# PCB_Design.net
KiCad netlist of a schematic drawn in EAGLE
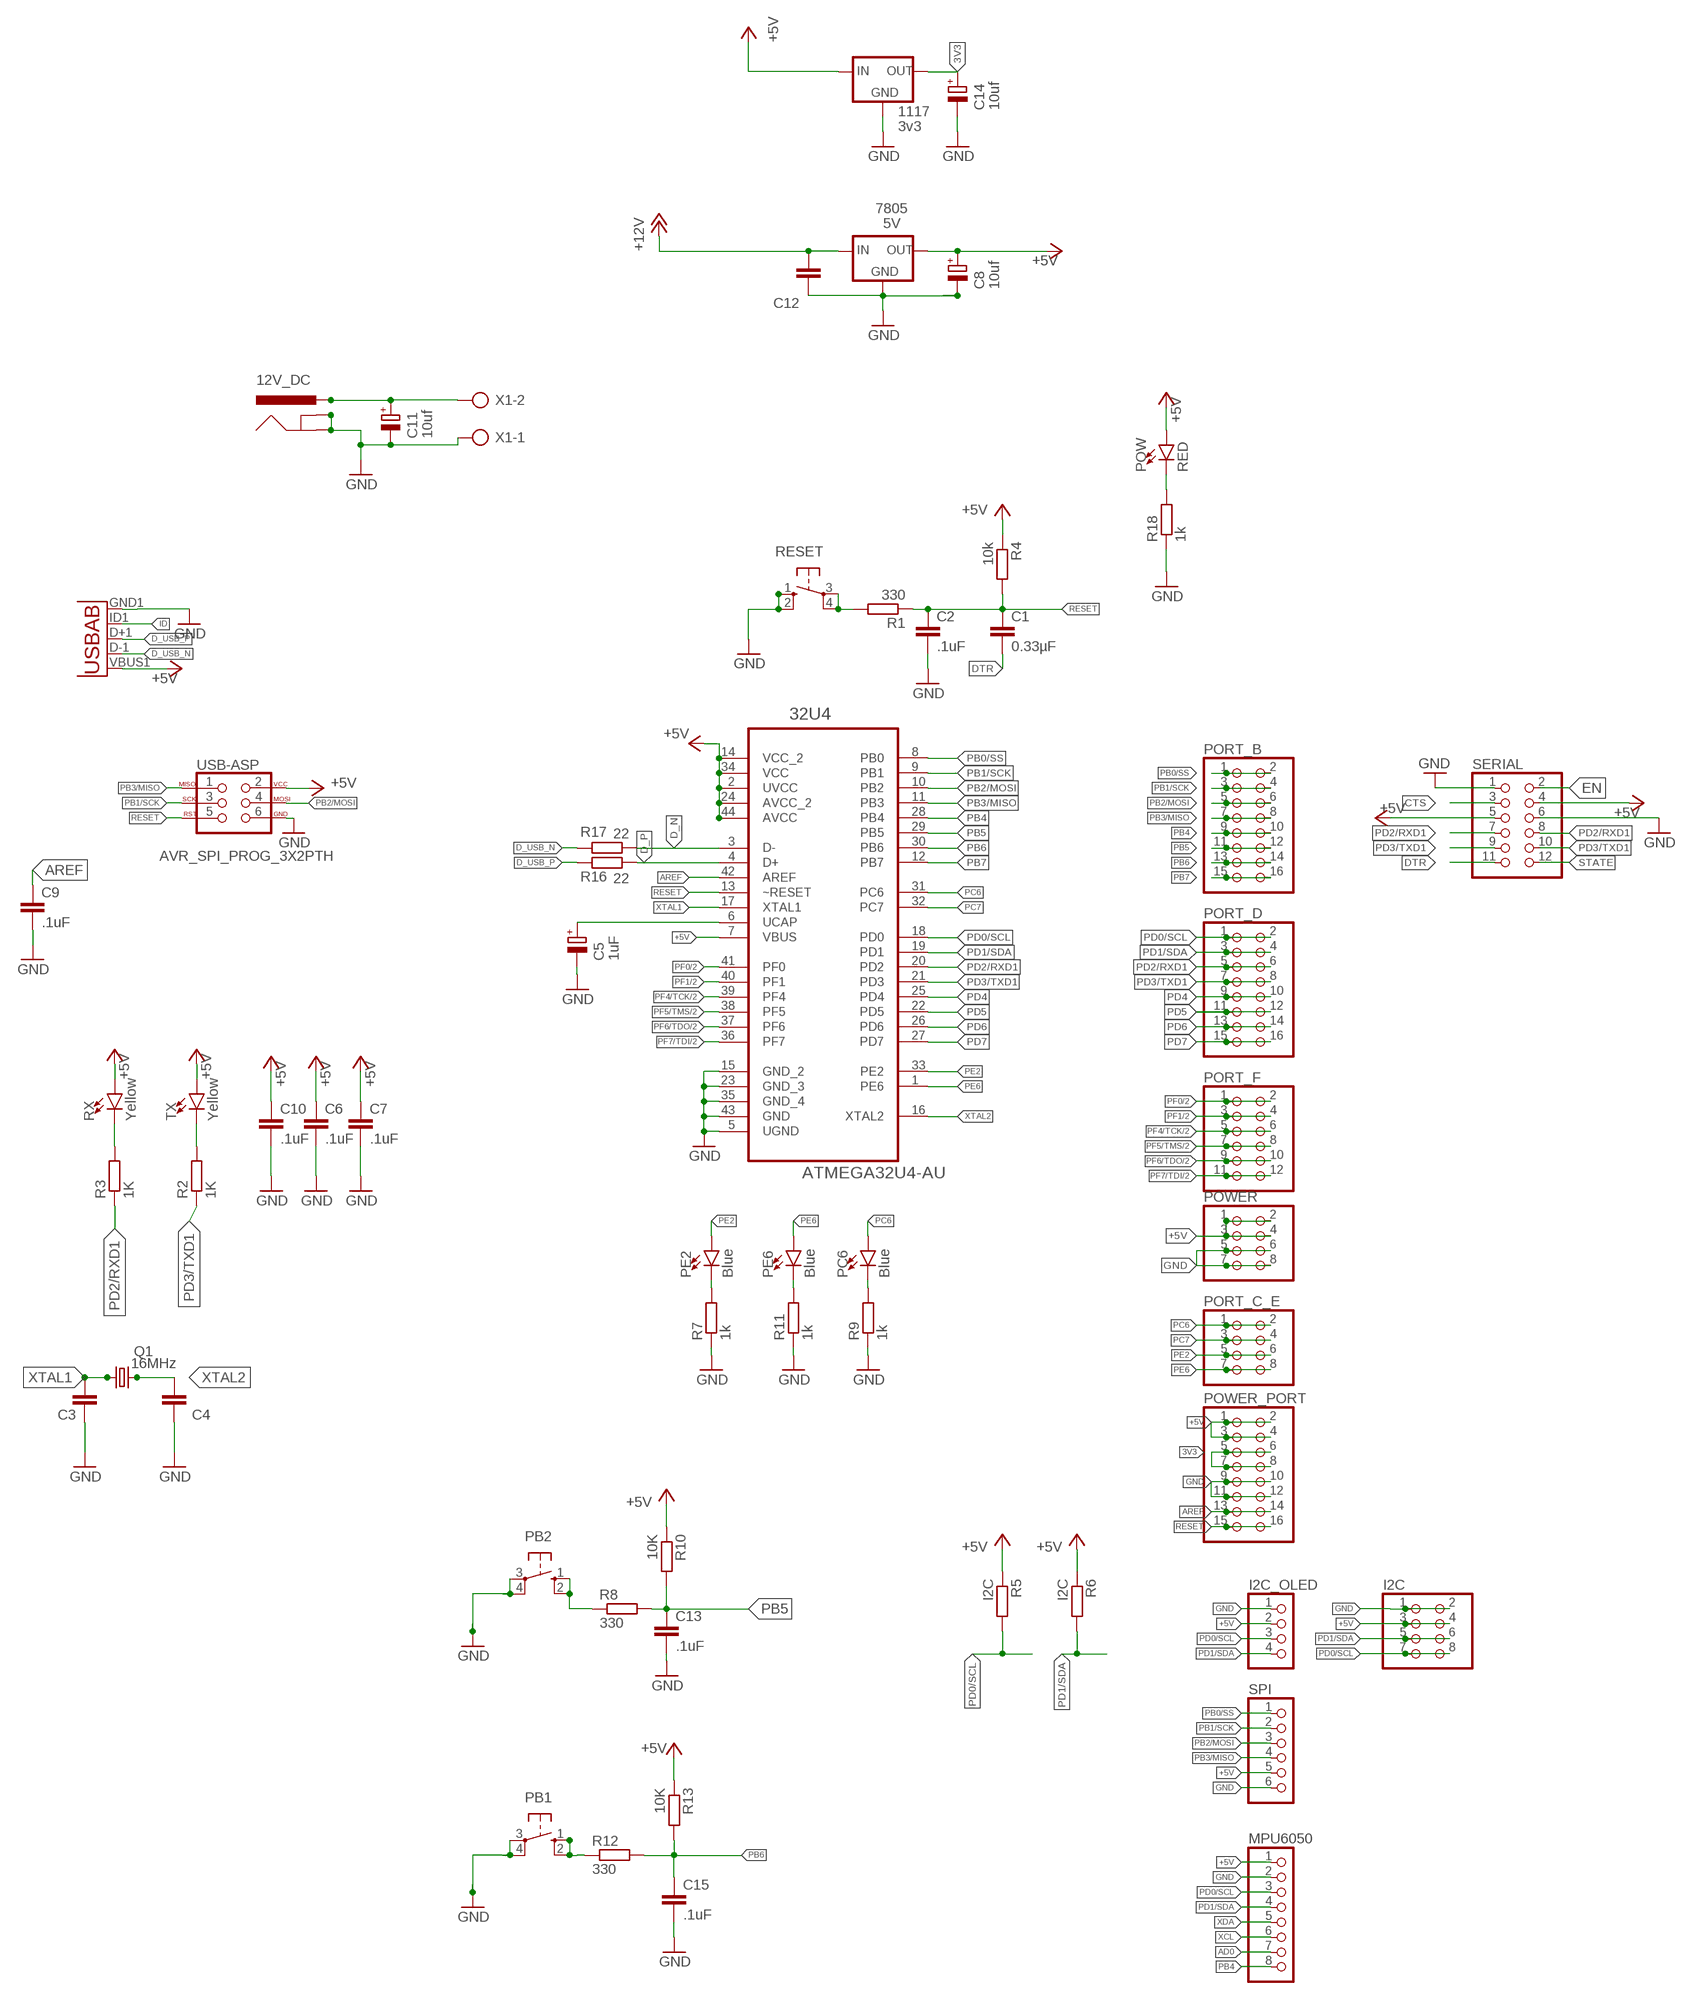
[diagram p0: schematic, sheet 1]
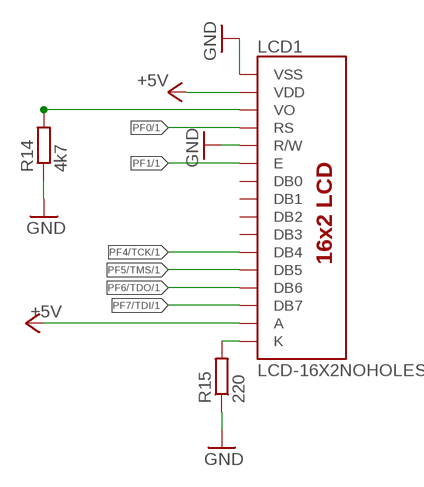
[diagram p1: schematic, sheet 2]

(export (version "E")
  (design (tool "Eeschema 10.0.6"))
  (components
    (comp (ref "LCD1")
      (value "LCD-16X2NOHOLES")
      (footprint "eagle-import:LCD-16X2_NOHOLESNOSILK")
      (libsource (lib "eagle-import") (part "LCD-16X2NOHOLES"))
    )
    (comp (ref "R14")
      (value "4k7")
      (footprint "eagle-import:M0805")
      (libsource (lib "eagle-import") (part "R-EU_M0805"))
    )
    (comp (ref "R15")
      (value "220")
      (footprint "eagle-import:M0805")
      (libsource (lib "eagle-import") (part "R-EU_M0805"))
    )
    (comp (ref "12V_DC")
      (value "POWER_JACK")
      (footprint "eagle-import:POWER_JACK_PTH")
      (fields (field (name "MF") "MULTICOMP") (field (name "MPN") "SPC21365"))
      (libsource (lib "eagle-import") (part "POWER_JACK"))
    )
    (comp (ref "32U4")
      (value "ATMEGA32U4-AU")
      (footprint "eagle-import:QFP80P1200X1200X120-44N")
      (fields (field (name "MF") "Microchip"))
      (libsource (lib "eagle-import") (part "ATMEGA32U4-AU"))
    )
    (comp (ref "1117")
      (value "3v3")
      (footprint "eagle-import:SOT223")
      (libsource (lib "eagle-import") (part "V_REG_LD1117VXXLD1117-SMD"))
    )
    (comp (ref "7805")
      (value "5V")
      (footprint "eagle-import:TO-252")
      (libsource (lib "eagle-import") (part "V_REG_78XX7812"))
    )
    (comp (ref "C1")
      (value "0.33µF")
      (footprint "eagle-import:C0805K")
      (libsource (lib "eagle-import") (part "C-EUC0805K"))
    )
    (comp (ref "C2")
      (value ".1uF")
      (footprint "eagle-import:C0805K")
      (libsource (lib "eagle-import") (part "C-EUC0805K"))
    )
    (comp (ref "C3")
      (value "22pF")
      (footprint "eagle-import:C0805K")
      (libsource (lib "eagle-import") (part "C-EUC0805K"))
    )
    (comp (ref "C4")
      (value "22pF")
      (footprint "eagle-import:C0805K")
      (libsource (lib "eagle-import") (part "C-EUC0805K"))
    )
    (comp (ref "C5")
      (value "1uF")
      (footprint "eagle-import:E2,5-6")
      (libsource (lib "eagle-import") (part "CPOL-EUE2.5-6"))
    )
    (comp (ref "C6")
      (value ".1uF")
      (footprint "eagle-import:C0805K")
      (libsource (lib "eagle-import") (part "C-EUC0805K"))
    )
    (comp (ref "C7")
      (value ".1uF")
      (footprint "eagle-import:C0805K")
      (libsource (lib "eagle-import") (part "C-EUC0805K"))
    )
    (comp (ref "C8")
      (value "10uf")
      (footprint "eagle-import:E2,5-6")
      (libsource (lib "eagle-import") (part "CPOL-EUE2.5-6"))
    )
    (comp (ref "C9")
      (value ".1uF")
      (footprint "eagle-import:C0805K")
      (libsource (lib "eagle-import") (part "C-EUC0805K"))
    )
    (comp (ref "C10")
      (value ".1uF")
      (footprint "eagle-import:C0805K")
      (libsource (lib "eagle-import") (part "C-EUC0805K"))
    )
    (comp (ref "C11")
      (value "10uf")
      (footprint "eagle-import:E2,5-6")
      (libsource (lib "eagle-import") (part "CPOL-EUE2.5-6"))
    )
    (comp (ref "C12")
      (value ".1uf")
      (footprint "eagle-import:C0805K")
      (libsource (lib "eagle-import") (part "C-EUC0805K"))
    )
    (comp (ref "C13")
      (value ".1uF")
      (footprint "eagle-import:C0805K")
      (libsource (lib "eagle-import") (part "C-EUC0805K"))
    )
    (comp (ref "C14")
      (value "10uf")
      (footprint "eagle-import:E2,5-6")
      (libsource (lib "eagle-import") (part "CPOL-EUE2.5-6"))
    )
    (comp (ref "C15")
      (value ".1uF")
      (footprint "eagle-import:C0805K")
      (libsource (lib "eagle-import") (part "C-EUC0805K"))
    )
    (comp (ref "I2C")
      (value "PINHD-2X4")
      (footprint "eagle-import:2X04")
      (libsource (lib "eagle-import") (part "PINHD-2X4"))
    )
    (comp (ref "I2C_OLED")
      (value "PINHD-1X4")
      (footprint "eagle-import:1X04")
      (libsource (lib "eagle-import") (part "PINHD-1X4"))
    )
    (comp (ref "MPU6050")
      (value "PINHD-1X8")
      (footprint "eagle-import:1X08")
      (libsource (lib "eagle-import") (part "PINHD-1X8"))
    )
    (comp (ref "PB1")
      (value "10-XX")
      (footprint "eagle-import:B3F-10XX")
      (fields (field (name "MPN") "B3F-1000") (field (name "MF") "OMRON"))
      (libsource (lib "eagle-import") (part "10-XX"))
    )
    (comp (ref "PB2")
      (value "10-XX")
      (footprint "eagle-import:B3F-10XX")
      (fields (field (name "MPN") "B3F-1000") (field (name "MF") "OMRON"))
      (libsource (lib "eagle-import") (part "10-XX"))
    )
    (comp (ref "PC6")
      (value "Blue")
      (footprint "eagle-import:LED-0603")
      (libsource (lib "eagle-import") (part "LED-BLUE0603"))
    )
    (comp (ref "PE2")
      (value "Blue")
      (footprint "eagle-import:LED-0603")
      (libsource (lib "eagle-import") (part "LED-BLUE0603"))
    )
    (comp (ref "PE6")
      (value "Blue")
      (footprint "eagle-import:LED-0603")
      (libsource (lib "eagle-import") (part "LED-BLUE0603"))
    )
    (comp (ref "PORT_B")
      (value "PINHD-2X8")
      (footprint "eagle-import:2X08")
      (libsource (lib "eagle-import") (part "PINHD-2X8"))
    )
    (comp (ref "PORT_C_E")
      (value "PINHD-2X4")
      (footprint "eagle-import:2X04")
      (libsource (lib "eagle-import") (part "PINHD-2X4"))
    )
    (comp (ref "PORT_D")
      (value "PINHD-2X8")
      (footprint "eagle-import:2X08")
      (libsource (lib "eagle-import") (part "PINHD-2X8"))
    )
    (comp (ref "PORT_F")
      (value "PINHD-2X6")
      (footprint "eagle-import:2X06")
      (libsource (lib "eagle-import") (part "PINHD-2X6"))
    )
    (comp (ref "POW")
      (value "RED")
      (footprint "eagle-import:LED-0603")
      (libsource (lib "eagle-import") (part "LED-BLUE0603"))
    )
    (comp (ref "POWER")
      (value "PINHD-2X4")
      (footprint "eagle-import:2X04")
      (libsource (lib "eagle-import") (part "PINHD-2X4"))
    )
    (comp (ref "POWER_PORT")
      (value "PINHD-2X8")
      (footprint "eagle-import:2X08")
      (libsource (lib "eagle-import") (part "PINHD-2X8"))
    )
    (comp (ref "Q1")
      (value "16MHz")
      (footprint "eagle-import:HC49U70")
      (libsource (lib "eagle-import") (part "CRYSTALHC49U70"))
    )
    (comp (ref "R1")
      (value "330")
      (footprint "eagle-import:M0805")
      (libsource (lib "eagle-import") (part "R-EU_M0805"))
    )
    (comp (ref "R2")
      (value "1K")
      (footprint "eagle-import:M0805")
      (libsource (lib "eagle-import") (part "R-EU_M0805"))
    )
    (comp (ref "R3")
      (value "1K")
      (footprint "eagle-import:M0805")
      (libsource (lib "eagle-import") (part "R-EU_M0805"))
    )
    (comp (ref "R4")
      (value "10k")
      (footprint "eagle-import:M0805")
      (libsource (lib "eagle-import") (part "R-EU_M0805"))
    )
    (comp (ref "R5")
      (value "I2C")
      (footprint "eagle-import:M0805")
      (libsource (lib "eagle-import") (part "R-EU_M0805"))
    )
    (comp (ref "R6")
      (value "I2C")
      (footprint "eagle-import:M0805")
      (libsource (lib "eagle-import") (part "R-EU_M0805"))
    )
    (comp (ref "R7")
      (value "1k")
      (footprint "eagle-import:M0805")
      (libsource (lib "eagle-import") (part "R-EU_M0805"))
    )
    (comp (ref "R8")
      (value "330")
      (footprint "eagle-import:M0805")
      (libsource (lib "eagle-import") (part "R-EU_M0805"))
    )
    (comp (ref "R9")
      (value "1k")
      (footprint "eagle-import:M0805")
      (libsource (lib "eagle-import") (part "R-EU_M0805"))
    )
    (comp (ref "R10")
      (value "10K")
      (footprint "eagle-import:M0805")
      (libsource (lib "eagle-import") (part "R-EU_M0805"))
    )
    (comp (ref "R11")
      (value "1k")
      (footprint "eagle-import:M0805")
      (libsource (lib "eagle-import") (part "R-EU_M0805"))
    )
    (comp (ref "R12")
      (value "330")
      (footprint "eagle-import:M0805")
      (libsource (lib "eagle-import") (part "R-EU_M0805"))
    )
    (comp (ref "R13")
      (value "10K")
      (footprint "eagle-import:M0805")
      (libsource (lib "eagle-import") (part "R-EU_M0805"))
    )
    (comp (ref "R16")
      (value "22")
      (footprint "eagle-import:M0805")
      (libsource (lib "eagle-import") (part "R-EU_M0805"))
    )
    (comp (ref "R17")
      (value "22")
      (footprint "eagle-import:M0805")
      (libsource (lib "eagle-import") (part "R-EU_M0805"))
    )
    (comp (ref "R18")
      (value "1k")
      (footprint "eagle-import:M0805")
      (libsource (lib "eagle-import") (part "R-EU_M0805"))
    )
    (comp (ref "RESET")
      (value "10-XX")
      (footprint "eagle-import:B3F-10XX")
      (fields (field (name "MPN") "B3F-1000") (field (name "MF") "OMRON"))
      (libsource (lib "eagle-import") (part "10-XX"))
    )
    (comp (ref "RX")
      (value "Yellow")
      (footprint "eagle-import:LED-0603")
      (libsource (lib "eagle-import") (part "LED-BLUE0603"))
    )
    (comp (ref "SERIAL")
      (value "PINHD-2X6")
      (footprint "eagle-import:2X06")
      (libsource (lib "eagle-import") (part "PINHD-2X6"))
    )
    (comp (ref "SPI")
      (value "PINHD-1X6")
      (footprint "eagle-import:1X06")
      (libsource (lib "eagle-import") (part "PINHD-1X6"))
    )
    (comp (ref "TX")
      (value "Yellow")
      (footprint "eagle-import:LED-0603")
      (libsource (lib "eagle-import") (part "LED-BLUE0603"))
    )
    (comp (ref "U1")
      (value "USB\"\"")
      (footprint "eagle-import:USB-MICRO-SMD")
      (libsource (lib "eagle-import") (part "USB{dblquote}{dblquote}"))
    )
    (comp (ref "USB-ASP")
      (value "AVR_SPI_PROG_3X2PTH")
      (footprint "eagle-import:2X3")
      (libsource (lib "eagle-import") (part "AVR_SPI_PROG_3X2PTH"))
    )
    (comp (ref "X1")
      (value "AK500/2-H")
      (footprint "eagle-import:AK500_2-H")
      (libsource (lib "eagle-import") (part "AK500/2-H"))
    )
  )
  (nets
    (net (code "1") (name "+5V") (class "Default")
      (node (ref "1117") (pin "3") (pinfunction "IN_3") (pintype "input"))
      (node (ref "32U4") (pin "14") (pinfunction "VCC_2_14") (pintype "power_in"))
      (node (ref "32U4") (pin "2") (pinfunction "UVCC_2") (pintype "power_in"))
      (node (ref "32U4") (pin "24") (pinfunction "AVCC_2_24") (pintype "power_in"))
      (node (ref "32U4") (pin "34") (pinfunction "VCC_34") (pintype "power_in"))
      (node (ref "32U4") (pin "44") (pinfunction "AVCC_44") (pintype "power_in"))
      (node (ref "32U4") (pin "7") (pinfunction "VBUS_7") (pintype "input"))
      (node (ref "7805") (pin "2") (pinfunction "OUT_2") (pintype "passive"))
      (node (ref "C10") (pin "1") (pinfunction "1_1") (pintype "passive"))
      (node (ref "C6") (pin "1") (pinfunction "1_1") (pintype "passive"))
      (node (ref "C7") (pin "1") (pinfunction "1_1") (pintype "passive"))
      (node (ref "C8") (pin "+") (pinfunction "+_+") (pintype "passive"))
      (node (ref "I2C") (pin "3") (pinfunction "3_3") (pintype "passive"))
      (node (ref "I2C") (pin "4") (pinfunction "4_4") (pintype "passive"))
      (node (ref "I2C_OLED") (pin "2") (pinfunction "2_2") (pintype "passive"))
      (node (ref "LCD1") (pin "15") (pinfunction "A_15") (pintype "power_in"))
      (node (ref "LCD1") (pin "2") (pinfunction "VDD_2") (pintype "power_in"))
      (node (ref "MPU6050") (pin "1") (pinfunction "1_1") (pintype "passive"))
      (node (ref "POW") (pin "A") (pinfunction "A_A") (pintype "passive"))
      (node (ref "POWER") (pin "1") (pinfunction "1_1") (pintype "passive"))
      (node (ref "POWER") (pin "2") (pinfunction "2_2") (pintype "passive"))
      (node (ref "POWER") (pin "3") (pinfunction "3_3") (pintype "passive"))
      (node (ref "POWER") (pin "4") (pinfunction "4_4") (pintype "passive"))
      (node (ref "POWER_PORT") (pin "1") (pinfunction "1_1") (pintype "passive"))
      (node (ref "POWER_PORT") (pin "2") (pinfunction "2_2") (pintype "passive"))
      (node (ref "POWER_PORT") (pin "3") (pinfunction "3_3") (pintype "passive"))
      (node (ref "POWER_PORT") (pin "4") (pinfunction "4_4") (pintype "passive"))
      (node (ref "R10") (pin "1") (pinfunction "1_1") (pintype "passive"))
      (node (ref "R13") (pin "1") (pinfunction "1_1") (pintype "passive"))
      (node (ref "R4") (pin "1") (pinfunction "1_1") (pintype "passive"))
      (node (ref "R5") (pin "1") (pinfunction "1_1") (pintype "passive"))
      (node (ref "R6") (pin "1") (pinfunction "1_1") (pintype "passive"))
      (node (ref "RX") (pin "A") (pinfunction "A_A") (pintype "passive"))
      (node (ref "SERIAL") (pin "4") (pinfunction "4_4") (pintype "passive"))
      (node (ref "SERIAL") (pin "5") (pinfunction "5_5") (pintype "passive"))
      (node (ref "SPI") (pin "5") (pinfunction "5_5") (pintype "passive"))
      (node (ref "TX") (pin "A") (pinfunction "A_A") (pintype "passive"))
      (node (ref "U1") (pin "VBUS1") (pinfunction "VBUS_VBUS1") (pintype "bidirectional"))
      (node (ref "USB-ASP") (pin "2") (pinfunction "2_2") (pintype "passive"))
    )
    (net (code "2") (name "+12V") (class "Default")
      (node (ref "12V_DC") (pin "PWR") (pinfunction "PWR_PWR") (pintype "bidirectional"))
      (node (ref "7805") (pin "1") (pinfunction "IN_1") (pintype "input"))
      (node (ref "C11") (pin "+") (pinfunction "+_+") (pintype "passive"))
      (node (ref "C12") (pin "1") (pinfunction "1_1") (pintype "passive"))
      (node (ref "X1") (pin "2") (pinfunction "KL_2") (pintype "passive"))
    )
    (net (code "3") (name "3V3") (class "Default")
      (node (ref "1117") (pin "2") (pinfunction "OUT_2") (pintype "passive"))
      (node (ref "C14") (pin "+") (pinfunction "+_+") (pintype "passive"))
      (node (ref "POWER_PORT") (pin "5") (pinfunction "5_5") (pintype "passive"))
      (node (ref "POWER_PORT") (pin "6") (pinfunction "6_6") (pintype "passive"))
      (node (ref "POWER_PORT") (pin "7") (pinfunction "7_7") (pintype "passive"))
      (node (ref "POWER_PORT") (pin "8") (pinfunction "8_8") (pintype "passive"))
    )
    (net (code "4") (name "AD0") (class "Default")
      (node (ref "MPU6050") (pin "7") (pinfunction "7_7") (pintype "passive"))
    )
    (net (code "5") (name "AREF") (class "Default")
      (node (ref "32U4") (pin "42") (pinfunction "AREF_42") (pintype "input"))
      (node (ref "C9") (pin "1") (pinfunction "1_1") (pintype "passive"))
      (node (ref "POWER_PORT") (pin "13") (pinfunction "13_13") (pintype "passive"))
      (node (ref "POWER_PORT") (pin "14") (pinfunction "14_14") (pintype "passive"))
    )
    (net (code "6") (name "CTS") (class "Default")
      (node (ref "SERIAL") (pin "3") (pinfunction "3_3") (pintype "passive"))
    )
    (net (code "7") (name "DTR") (class "Default")
      (node (ref "C1") (pin "2") (pinfunction "2_2") (pintype "passive"))
      (node (ref "SERIAL") (pin "11") (pinfunction "11_11") (pintype "passive"))
    )
    (net (code "8") (name "D_N") (class "Default")
      (node (ref "32U4") (pin "3") (pinfunction "D-_3") (pintype "passive"))
      (node (ref "R17") (pin "1") (pinfunction "1_1") (pintype "passive"))
    )
    (net (code "9") (name "D_P") (class "Default")
      (node (ref "32U4") (pin "4") (pinfunction "D+_4") (pintype "passive"))
      (node (ref "R16") (pin "1") (pinfunction "1_1") (pintype "passive"))
    )
    (net (code "10") (name "D_USB_N") (class "Default")
      (node (ref "R17") (pin "2") (pinfunction "2_2") (pintype "passive"))
      (node (ref "U1") (pin "D-1") (pinfunction "D-_D-1") (pintype "bidirectional"))
    )
    (net (code "11") (name "D_USB_P") (class "Default")
      (node (ref "R16") (pin "2") (pinfunction "2_2") (pintype "passive"))
      (node (ref "U1") (pin "D+1") (pinfunction "D+_D+1") (pintype "bidirectional"))
    )
    (net (code "12") (name "EN") (class "Default")
      (node (ref "SERIAL") (pin "2") (pinfunction "2_2") (pintype "passive"))
    )
    (net (code "13") (name "GND") (class "Default")
      (node (ref "1117") (pin "1") (pinfunction "GND_1") (pintype "input"))
      (node (ref "12V_DC") (pin "GND") (pinfunction "GND_GND") (pintype "bidirectional"))
      (node (ref "12V_DC") (pin "GNDBREAK") (pinfunction "GNDBREAK_GNDBREAK") (pintype "bidirectional"))
      (node (ref "32U4") (pin "15") (pinfunction "GND_2_15") (pintype "passive"))
      (node (ref "32U4") (pin "23") (pinfunction "GND_3_23") (pintype "passive"))
      (node (ref "32U4") (pin "35") (pinfunction "GND_4_35") (pintype "passive"))
      (node (ref "32U4") (pin "43") (pinfunction "GND_43") (pintype "passive"))
      (node (ref "32U4") (pin "5") (pinfunction "UGND_5") (pintype "passive"))
      (node (ref "7805") (pin "3") (pinfunction "GND_3") (pintype "input"))
      (node (ref "C10") (pin "2") (pinfunction "2_2") (pintype "passive"))
      (node (ref "C11") (pin "-") (pinfunction "-_-") (pintype "passive"))
      (node (ref "C12") (pin "2") (pinfunction "2_2") (pintype "passive"))
      (node (ref "C13") (pin "2") (pinfunction "2_2") (pintype "passive"))
      (node (ref "C14") (pin "-") (pinfunction "-_-") (pintype "passive"))
      (node (ref "C15") (pin "2") (pinfunction "2_2") (pintype "passive"))
      (node (ref "C2") (pin "2") (pinfunction "2_2") (pintype "passive"))
      (node (ref "C3") (pin "1") (pinfunction "1_1") (pintype "passive"))
      (node (ref "C4") (pin "1") (pinfunction "1_1") (pintype "passive"))
      (node (ref "C5") (pin "-") (pinfunction "-_-") (pintype "passive"))
      (node (ref "C6") (pin "2") (pinfunction "2_2") (pintype "passive"))
      (node (ref "C7") (pin "2") (pinfunction "2_2") (pintype "passive"))
      (node (ref "C8") (pin "-") (pinfunction "-_-") (pintype "passive"))
      (node (ref "C9") (pin "2") (pinfunction "2_2") (pintype "passive"))
      (node (ref "I2C") (pin "1") (pinfunction "1_1") (pintype "passive"))
      (node (ref "I2C") (pin "2") (pinfunction "2_2") (pintype "passive"))
      (node (ref "I2C_OLED") (pin "1") (pinfunction "1_1") (pintype "passive"))
      (node (ref "LCD1") (pin "1") (pinfunction "VSS_1") (pintype "power_in"))
      (node (ref "LCD1") (pin "5") (pinfunction "R/W_5") (pintype "input"))
      (node (ref "MPU6050") (pin "2") (pinfunction "2_2") (pintype "passive"))
      (node (ref "PB1") (pin "3") (pinfunction "P_3") (pintype "passive"))
      (node (ref "PB1") (pin "4") (pinfunction "P1_4") (pintype "passive"))
      (node (ref "PB2") (pin "3") (pinfunction "P_3") (pintype "passive"))
      (node (ref "PB2") (pin "4") (pinfunction "P1_4") (pintype "passive"))
      (node (ref "POWER") (pin "5") (pinfunction "5_5") (pintype "passive"))
      (node (ref "POWER") (pin "6") (pinfunction "6_6") (pintype "passive"))
      (node (ref "POWER") (pin "7") (pinfunction "7_7") (pintype "passive"))
      (node (ref "POWER") (pin "8") (pinfunction "8_8") (pintype "passive"))
      (node (ref "POWER_PORT") (pin "10") (pinfunction "10_10") (pintype "passive"))
      (node (ref "POWER_PORT") (pin "11") (pinfunction "11_11") (pintype "passive"))
      (node (ref "POWER_PORT") (pin "12") (pinfunction "12_12") (pintype "passive"))
      (node (ref "POWER_PORT") (pin "9") (pinfunction "9_9") (pintype "passive"))
      (node (ref "R11") (pin "1") (pinfunction "1_1") (pintype "passive"))
      (node (ref "R14") (pin "1") (pinfunction "1_1") (pintype "passive"))
      (node (ref "R15") (pin "1") (pinfunction "1_1") (pintype "passive"))
      (node (ref "R18") (pin "1") (pinfunction "1_1") (pintype "passive"))
      (node (ref "R7") (pin "1") (pinfunction "1_1") (pintype "passive"))
      (node (ref "R9") (pin "1") (pinfunction "1_1") (pintype "passive"))
      (node (ref "RESET") (pin "1") (pinfunction "S_1") (pintype "passive"))
      (node (ref "RESET") (pin "2") (pinfunction "S1_2") (pintype "passive"))
      (node (ref "SERIAL") (pin "1") (pinfunction "1_1") (pintype "passive"))
      (node (ref "SERIAL") (pin "6") (pinfunction "6_6") (pintype "passive"))
      (node (ref "SPI") (pin "6") (pinfunction "6_6") (pintype "passive"))
      (node (ref "U1") (pin "GND1") (pinfunction "GND_GND1") (pintype "bidirectional"))
      (node (ref "USB-ASP") (pin "6") (pinfunction "6_6") (pintype "passive"))
      (node (ref "X1") (pin "1") (pinfunction "KL_1") (pintype "passive"))
    )
    (net (code "14") (name "ID") (class "Default")
      (node (ref "U1") (pin "ID1") (pinfunction "USBID_ID1") (pintype "bidirectional"))
    )
    (net (code "15") (name "Net-(32U4-UCAP)") (class "Default")
      (node (ref "32U4") (pin "6") (pinfunction "UCAP_6") (pintype "power_in"))
      (node (ref "C5") (pin "+") (pinfunction "+_+") (pintype "passive"))
    )
    (net (code "16") (name "Net-(LCD1-K)") (class "Default")
      (node (ref "LCD1") (pin "16") (pinfunction "K_16") (pintype "power_in"))
      (node (ref "R15") (pin "2") (pinfunction "2_2") (pintype "passive"))
    )
    (net (code "17") (name "Net-(LCD1-VO)") (class "Default")
      (node (ref "LCD1") (pin "3") (pinfunction "VO_3") (pintype "bidirectional"))
      (node (ref "R14") (pin "2") (pinfunction "2_2") (pintype "passive"))
    )
    (net (code "18") (name "Net-(PB1-S)") (class "Default")
      (node (ref "PB1") (pin "1") (pinfunction "S_1") (pintype "passive"))
      (node (ref "PB1") (pin "2") (pinfunction "S1_2") (pintype "passive"))
      (node (ref "R12") (pin "1") (pinfunction "1_1") (pintype "passive"))
    )
    (net (code "19") (name "Net-(PB2-S)") (class "Default")
      (node (ref "PB2") (pin "1") (pinfunction "S_1") (pintype "passive"))
      (node (ref "PB2") (pin "2") (pinfunction "S1_2") (pintype "passive"))
      (node (ref "R8") (pin "1") (pinfunction "1_1") (pintype "passive"))
    )
    (net (code "20") (name "Net-(PC6-PadC)") (class "Default")
      (node (ref "PC6") (pin "C") (pinfunction "C_C") (pintype "passive"))
      (node (ref "R9") (pin "2") (pinfunction "2_2") (pintype "passive"))
    )
    (net (code "21") (name "Net-(PE2-PadC)") (class "Default")
      (node (ref "PE2") (pin "C") (pinfunction "C_C") (pintype "passive"))
      (node (ref "R7") (pin "2") (pinfunction "2_2") (pintype "passive"))
    )
    (net (code "22") (name "Net-(PE6-PadC)") (class "Default")
      (node (ref "PE6") (pin "C") (pinfunction "C_C") (pintype "passive"))
      (node (ref "R11") (pin "2") (pinfunction "2_2") (pintype "passive"))
    )
    (net (code "23") (name "Net-(POW-PadC)") (class "Default")
      (node (ref "POW") (pin "C") (pinfunction "C_C") (pintype "passive"))
      (node (ref "R18") (pin "2") (pinfunction "2_2") (pintype "passive"))
    )
    (net (code "24") (name "Net-(R2-Pad2)") (class "Default")
      (node (ref "R2") (pin "2") (pinfunction "2_2") (pintype "passive"))
      (node (ref "TX") (pin "C") (pinfunction "C_C") (pintype "passive"))
    )
    (net (code "25") (name "Net-(R3-Pad2)") (class "Default")
      (node (ref "R3") (pin "2") (pinfunction "2_2") (pintype "passive"))
      (node (ref "RX") (pin "C") (pinfunction "C_C") (pintype "passive"))
    )
    (net (code "26") (name "Net-(RESET-P)") (class "Default")
      (node (ref "R1") (pin "2") (pinfunction "2_2") (pintype "passive"))
      (node (ref "RESET") (pin "3") (pinfunction "P_3") (pintype "passive"))
      (node (ref "RESET") (pin "4") (pinfunction "P1_4") (pintype "passive"))
    )
    (net (code "27") (name "PB0{slash}SS") (class "Default")
      (node (ref "32U4") (pin "8") (pinfunction "PB0_8") (pintype "bidirectional"))
      (node (ref "PORT_B") (pin "1") (pinfunction "1_1") (pintype "passive"))
      (node (ref "PORT_B") (pin "2") (pinfunction "2_2") (pintype "passive"))
      (node (ref "SPI") (pin "1") (pinfunction "1_1") (pintype "passive"))
    )
    (net (code "28") (name "PB1{slash}SCK") (class "Default")
      (node (ref "32U4") (pin "9") (pinfunction "PB1_9") (pintype "bidirectional"))
      (node (ref "PORT_B") (pin "3") (pinfunction "3_3") (pintype "passive"))
      (node (ref "PORT_B") (pin "4") (pinfunction "4_4") (pintype "passive"))
      (node (ref "SPI") (pin "2") (pinfunction "2_2") (pintype "passive"))
      (node (ref "USB-ASP") (pin "3") (pinfunction "3_3") (pintype "passive"))
    )
    (net (code "29") (name "PB2{slash}MOSI") (class "Default")
      (node (ref "32U4") (pin "10") (pinfunction "PB2_10") (pintype "bidirectional"))
      (node (ref "PORT_B") (pin "5") (pinfunction "5_5") (pintype "passive"))
      (node (ref "PORT_B") (pin "6") (pinfunction "6_6") (pintype "passive"))
      (node (ref "SPI") (pin "3") (pinfunction "3_3") (pintype "passive"))
      (node (ref "USB-ASP") (pin "4") (pinfunction "4_4") (pintype "passive"))
    )
    (net (code "30") (name "PB3{slash}MISO") (class "Default")
      (node (ref "32U4") (pin "11") (pinfunction "PB3_11") (pintype "bidirectional"))
      (node (ref "PORT_B") (pin "7") (pinfunction "7_7") (pintype "passive"))
      (node (ref "PORT_B") (pin "8") (pinfunction "8_8") (pintype "passive"))
      (node (ref "SPI") (pin "4") (pinfunction "4_4") (pintype "passive"))
      (node (ref "USB-ASP") (pin "1") (pinfunction "1_1") (pintype "passive"))
    )
    (net (code "31") (name "PB4") (class "Default")
      (node (ref "32U4") (pin "28") (pinfunction "PB4_28") (pintype "bidirectional"))
      (node (ref "MPU6050") (pin "8") (pinfunction "8_8") (pintype "passive"))
      (node (ref "PORT_B") (pin "10") (pinfunction "10_10") (pintype "passive"))
      (node (ref "PORT_B") (pin "9") (pinfunction "9_9") (pintype "passive"))
    )
    (net (code "32") (name "PB5") (class "Default")
      (node (ref "32U4") (pin "29") (pinfunction "PB5_29") (pintype "bidirectional"))
      (node (ref "C13") (pin "1") (pinfunction "1_1") (pintype "passive"))
      (node (ref "PORT_B") (pin "11") (pinfunction "11_11") (pintype "passive"))
      (node (ref "PORT_B") (pin "12") (pinfunction "12_12") (pintype "passive"))
      (node (ref "R10") (pin "2") (pinfunction "2_2") (pintype "passive"))
      (node (ref "R8") (pin "2") (pinfunction "2_2") (pintype "passive"))
    )
    (net (code "33") (name "PB6") (class "Default")
      (node (ref "32U4") (pin "30") (pinfunction "PB6_30") (pintype "bidirectional"))
      (node (ref "C15") (pin "1") (pinfunction "1_1") (pintype "passive"))
      (node (ref "PORT_B") (pin "13") (pinfunction "13_13") (pintype "passive"))
      (node (ref "PORT_B") (pin "14") (pinfunction "14_14") (pintype "passive"))
      (node (ref "R12") (pin "2") (pinfunction "2_2") (pintype "passive"))
      (node (ref "R13") (pin "2") (pinfunction "2_2") (pintype "passive"))
    )
    (net (code "34") (name "PB7") (class "Default")
      (node (ref "32U4") (pin "12") (pinfunction "PB7_12") (pintype "bidirectional"))
      (node (ref "PORT_B") (pin "15") (pinfunction "15_15") (pintype "passive"))
      (node (ref "PORT_B") (pin "16") (pinfunction "16_16") (pintype "passive"))
    )
    (net (code "35") (name "PC6") (class "Default")
      (node (ref "32U4") (pin "31") (pinfunction "PC6_31") (pintype "bidirectional"))
      (node (ref "PC6") (pin "A") (pinfunction "A_A") (pintype "passive"))
      (node (ref "PORT_C_E") (pin "1") (pinfunction "1_1") (pintype "passive"))
      (node (ref "PORT_C_E") (pin "2") (pinfunction "2_2") (pintype "passive"))
    )
    (net (code "36") (name "PC7") (class "Default")
      (node (ref "32U4") (pin "32") (pinfunction "PC7_32") (pintype "bidirectional"))
      (node (ref "PORT_C_E") (pin "3") (pinfunction "3_3") (pintype "passive"))
      (node (ref "PORT_C_E") (pin "4") (pinfunction "4_4") (pintype "passive"))
    )
    (net (code "37") (name "PD0{slash}SCL") (class "Default")
      (node (ref "32U4") (pin "18") (pinfunction "PD0_18") (pintype "bidirectional"))
      (node (ref "I2C") (pin "7") (pinfunction "7_7") (pintype "passive"))
      (node (ref "I2C") (pin "8") (pinfunction "8_8") (pintype "passive"))
      (node (ref "I2C_OLED") (pin "3") (pinfunction "3_3") (pintype "passive"))
      (node (ref "MPU6050") (pin "3") (pinfunction "3_3") (pintype "passive"))
      (node (ref "PORT_D") (pin "1") (pinfunction "1_1") (pintype "passive"))
      (node (ref "PORT_D") (pin "2") (pinfunction "2_2") (pintype "passive"))
      (node (ref "R5") (pin "2") (pinfunction "2_2") (pintype "passive"))
    )
    (net (code "38") (name "PD1{slash}SDA") (class "Default")
      (node (ref "32U4") (pin "19") (pinfunction "PD1_19") (pintype "bidirectional"))
      (node (ref "I2C") (pin "5") (pinfunction "5_5") (pintype "passive"))
      (node (ref "I2C") (pin "6") (pinfunction "6_6") (pintype "passive"))
      (node (ref "I2C_OLED") (pin "4") (pinfunction "4_4") (pintype "passive"))
      (node (ref "MPU6050") (pin "4") (pinfunction "4_4") (pintype "passive"))
      (node (ref "PORT_D") (pin "3") (pinfunction "3_3") (pintype "passive"))
      (node (ref "PORT_D") (pin "4") (pinfunction "4_4") (pintype "passive"))
      (node (ref "R6") (pin "2") (pinfunction "2_2") (pintype "passive"))
    )
    (net (code "39") (name "PD2{slash}RXD1") (class "Default")
      (node (ref "32U4") (pin "20") (pinfunction "PD2_20") (pintype "bidirectional"))
      (node (ref "PORT_D") (pin "5") (pinfunction "5_5") (pintype "passive"))
      (node (ref "PORT_D") (pin "6") (pinfunction "6_6") (pintype "passive"))
      (node (ref "R3") (pin "1") (pinfunction "1_1") (pintype "passive"))
      (node (ref "SERIAL") (pin "7") (pinfunction "7_7") (pintype "passive"))
      (node (ref "SERIAL") (pin "8") (pinfunction "8_8") (pintype "passive"))
    )
    (net (code "40") (name "PD3{slash}TXD1") (class "Default")
      (node (ref "32U4") (pin "21") (pinfunction "PD3_21") (pintype "bidirectional"))
      (node (ref "PORT_D") (pin "7") (pinfunction "7_7") (pintype "passive"))
      (node (ref "PORT_D") (pin "8") (pinfunction "8_8") (pintype "passive"))
      (node (ref "R2") (pin "1") (pinfunction "1_1") (pintype "passive"))
      (node (ref "SERIAL") (pin "10") (pinfunction "10_10") (pintype "passive"))
      (node (ref "SERIAL") (pin "9") (pinfunction "9_9") (pintype "passive"))
    )
    (net (code "41") (name "PD4") (class "Default")
      (node (ref "32U4") (pin "25") (pinfunction "PD4_25") (pintype "bidirectional"))
      (node (ref "PORT_D") (pin "10") (pinfunction "10_10") (pintype "passive"))
      (node (ref "PORT_D") (pin "9") (pinfunction "9_9") (pintype "passive"))
    )
    (net (code "42") (name "PD5") (class "Default")
      (node (ref "32U4") (pin "22") (pinfunction "PD5_22") (pintype "bidirectional"))
      (node (ref "PORT_D") (pin "11") (pinfunction "11_11") (pintype "passive"))
      (node (ref "PORT_D") (pin "12") (pinfunction "12_12") (pintype "passive"))
    )
    (net (code "43") (name "PD6") (class "Default")
      (node (ref "32U4") (pin "26") (pinfunction "PD6_26") (pintype "bidirectional"))
      (node (ref "PORT_D") (pin "13") (pinfunction "13_13") (pintype "passive"))
      (node (ref "PORT_D") (pin "14") (pinfunction "14_14") (pintype "passive"))
    )
    (net (code "44") (name "PD7") (class "Default")
      (node (ref "32U4") (pin "27") (pinfunction "PD7_27") (pintype "bidirectional"))
      (node (ref "PORT_D") (pin "15") (pinfunction "15_15") (pintype "passive"))
      (node (ref "PORT_D") (pin "16") (pinfunction "16_16") (pintype "passive"))
    )
    (net (code "45") (name "PE2") (class "Default")
      (node (ref "32U4") (pin "33") (pinfunction "PE2_33") (pintype "bidirectional"))
      (node (ref "PE2") (pin "A") (pinfunction "A_A") (pintype "passive"))
      (node (ref "PORT_C_E") (pin "5") (pinfunction "5_5") (pintype "passive"))
      (node (ref "PORT_C_E") (pin "6") (pinfunction "6_6") (pintype "passive"))
    )
    (net (code "46") (name "PE6") (class "Default")
      (node (ref "32U4") (pin "1") (pinfunction "PE6_1") (pintype "bidirectional"))
      (node (ref "PE6") (pin "A") (pinfunction "A_A") (pintype "passive"))
      (node (ref "PORT_C_E") (pin "7") (pinfunction "7_7") (pintype "passive"))
      (node (ref "PORT_C_E") (pin "8") (pinfunction "8_8") (pintype "passive"))
    )
    (net (code "47") (name "PF0") (class "Default")
      (node (ref "32U4") (pin "41") (pinfunction "PF0_41") (pintype "bidirectional"))
      (node (ref "LCD1") (pin "4") (pinfunction "RS_4") (pintype "input"))
      (node (ref "PORT_F") (pin "1") (pinfunction "1_1") (pintype "passive"))
      (node (ref "PORT_F") (pin "2") (pinfunction "2_2") (pintype "passive"))
    )
    (net (code "48") (name "PF1") (class "Default")
      (node (ref "32U4") (pin "40") (pinfunction "PF1_40") (pintype "bidirectional"))
      (node (ref "LCD1") (pin "6") (pinfunction "E_6") (pintype "input"))
      (node (ref "PORT_F") (pin "3") (pinfunction "3_3") (pintype "passive"))
      (node (ref "PORT_F") (pin "4") (pinfunction "4_4") (pintype "passive"))
    )
    (net (code "49") (name "PF4{slash}TCK") (class "Default")
      (node (ref "32U4") (pin "39") (pinfunction "PF4_39") (pintype "bidirectional"))
      (node (ref "LCD1") (pin "11") (pinfunction "DB4_11") (pintype "bidirectional"))
      (node (ref "PORT_F") (pin "5") (pinfunction "5_5") (pintype "passive"))
      (node (ref "PORT_F") (pin "6") (pinfunction "6_6") (pintype "passive"))
    )
    (net (code "50") (name "PF5{slash}TMS") (class "Default")
      (node (ref "32U4") (pin "38") (pinfunction "PF5_38") (pintype "bidirectional"))
      (node (ref "LCD1") (pin "12") (pinfunction "DB5_12") (pintype "bidirectional"))
      (node (ref "PORT_F") (pin "7") (pinfunction "7_7") (pintype "passive"))
      (node (ref "PORT_F") (pin "8") (pinfunction "8_8") (pintype "passive"))
    )
    (net (code "51") (name "PF6{slash}TDO") (class "Default")
      (node (ref "32U4") (pin "37") (pinfunction "PF6_37") (pintype "bidirectional"))
      (node (ref "LCD1") (pin "13") (pinfunction "DB6_13") (pintype "bidirectional"))
      (node (ref "PORT_F") (pin "10") (pinfunction "10_10") (pintype "passive"))
      (node (ref "PORT_F") (pin "9") (pinfunction "9_9") (pintype "passive"))
    )
    (net (code "52") (name "PF7{slash}TDI") (class "Default")
      (node (ref "32U4") (pin "36") (pinfunction "PF7_36") (pintype "bidirectional"))
      (node (ref "LCD1") (pin "14") (pinfunction "DB7_14") (pintype "bidirectional"))
      (node (ref "PORT_F") (pin "11") (pinfunction "11_11") (pintype "passive"))
      (node (ref "PORT_F") (pin "12") (pinfunction "12_12") (pintype "passive"))
    )
    (net (code "53") (name "RESET") (class "Default")
      (node (ref "32U4") (pin "13") (pinfunction "~{RESET}_13") (pintype "input"))
      (node (ref "C1") (pin "1") (pinfunction "1_1") (pintype "passive"))
      (node (ref "C2") (pin "1") (pinfunction "1_1") (pintype "passive"))
      (node (ref "POWER_PORT") (pin "15") (pinfunction "15_15") (pintype "passive"))
      (node (ref "POWER_PORT") (pin "16") (pinfunction "16_16") (pintype "passive"))
      (node (ref "R1") (pin "1") (pinfunction "1_1") (pintype "passive"))
      (node (ref "R4") (pin "2") (pinfunction "2_2") (pintype "passive"))
      (node (ref "USB-ASP") (pin "5") (pinfunction "5_5") (pintype "passive"))
    )
    (net (code "54") (name "STATE") (class "Default")
      (node (ref "SERIAL") (pin "12") (pinfunction "12_12") (pintype "passive"))
    )
    (net (code "55") (name "XCL") (class "Default")
      (node (ref "MPU6050") (pin "6") (pinfunction "6_6") (pintype "passive"))
    )
    (net (code "56") (name "XDA") (class "Default")
      (node (ref "MPU6050") (pin "5") (pinfunction "5_5") (pintype "passive"))
    )
    (net (code "57") (name "XTAL1") (class "Default")
      (node (ref "32U4") (pin "17") (pinfunction "XTAL1_17") (pintype "input"))
      (node (ref "C3") (pin "2") (pinfunction "2_2") (pintype "passive"))
      (node (ref "Q1") (pin "1") (pinfunction "1_1") (pintype "passive"))
    )
    (net (code "58") (name "XTAL2") (class "Default")
      (node (ref "32U4") (pin "16") (pinfunction "XTAL2_16") (pintype "output"))
      (node (ref "C4") (pin "2") (pinfunction "2_2") (pintype "passive"))
      (node (ref "Q1") (pin "2") (pinfunction "2_2") (pintype "passive"))
    )
    (net (code "59") (name "unconnected-(LCD1-DB0-Pad7)") (class "Default")
      (node (ref "LCD1") (pin "7") (pinfunction "DB0_7") (pintype "bidirectional"))
    )
    (net (code "60") (name "unconnected-(LCD1-DB1-Pad8)") (class "Default")
      (node (ref "LCD1") (pin "8") (pinfunction "DB1_8") (pintype "bidirectional"))
    )
    (net (code "61") (name "unconnected-(LCD1-DB2-Pad9)") (class "Default")
      (node (ref "LCD1") (pin "9") (pinfunction "DB2_9") (pintype "bidirectional"))
    )
    (net (code "62") (name "unconnected-(LCD1-DB3-Pad10)") (class "Default")
      (node (ref "LCD1") (pin "10") (pinfunction "DB3_10") (pintype "bidirectional"))
    )
  )
)
